# Adafruit_Airlift_Bitsy_Add-On.net
KiCad netlist of a schematic drawn in EAGLE
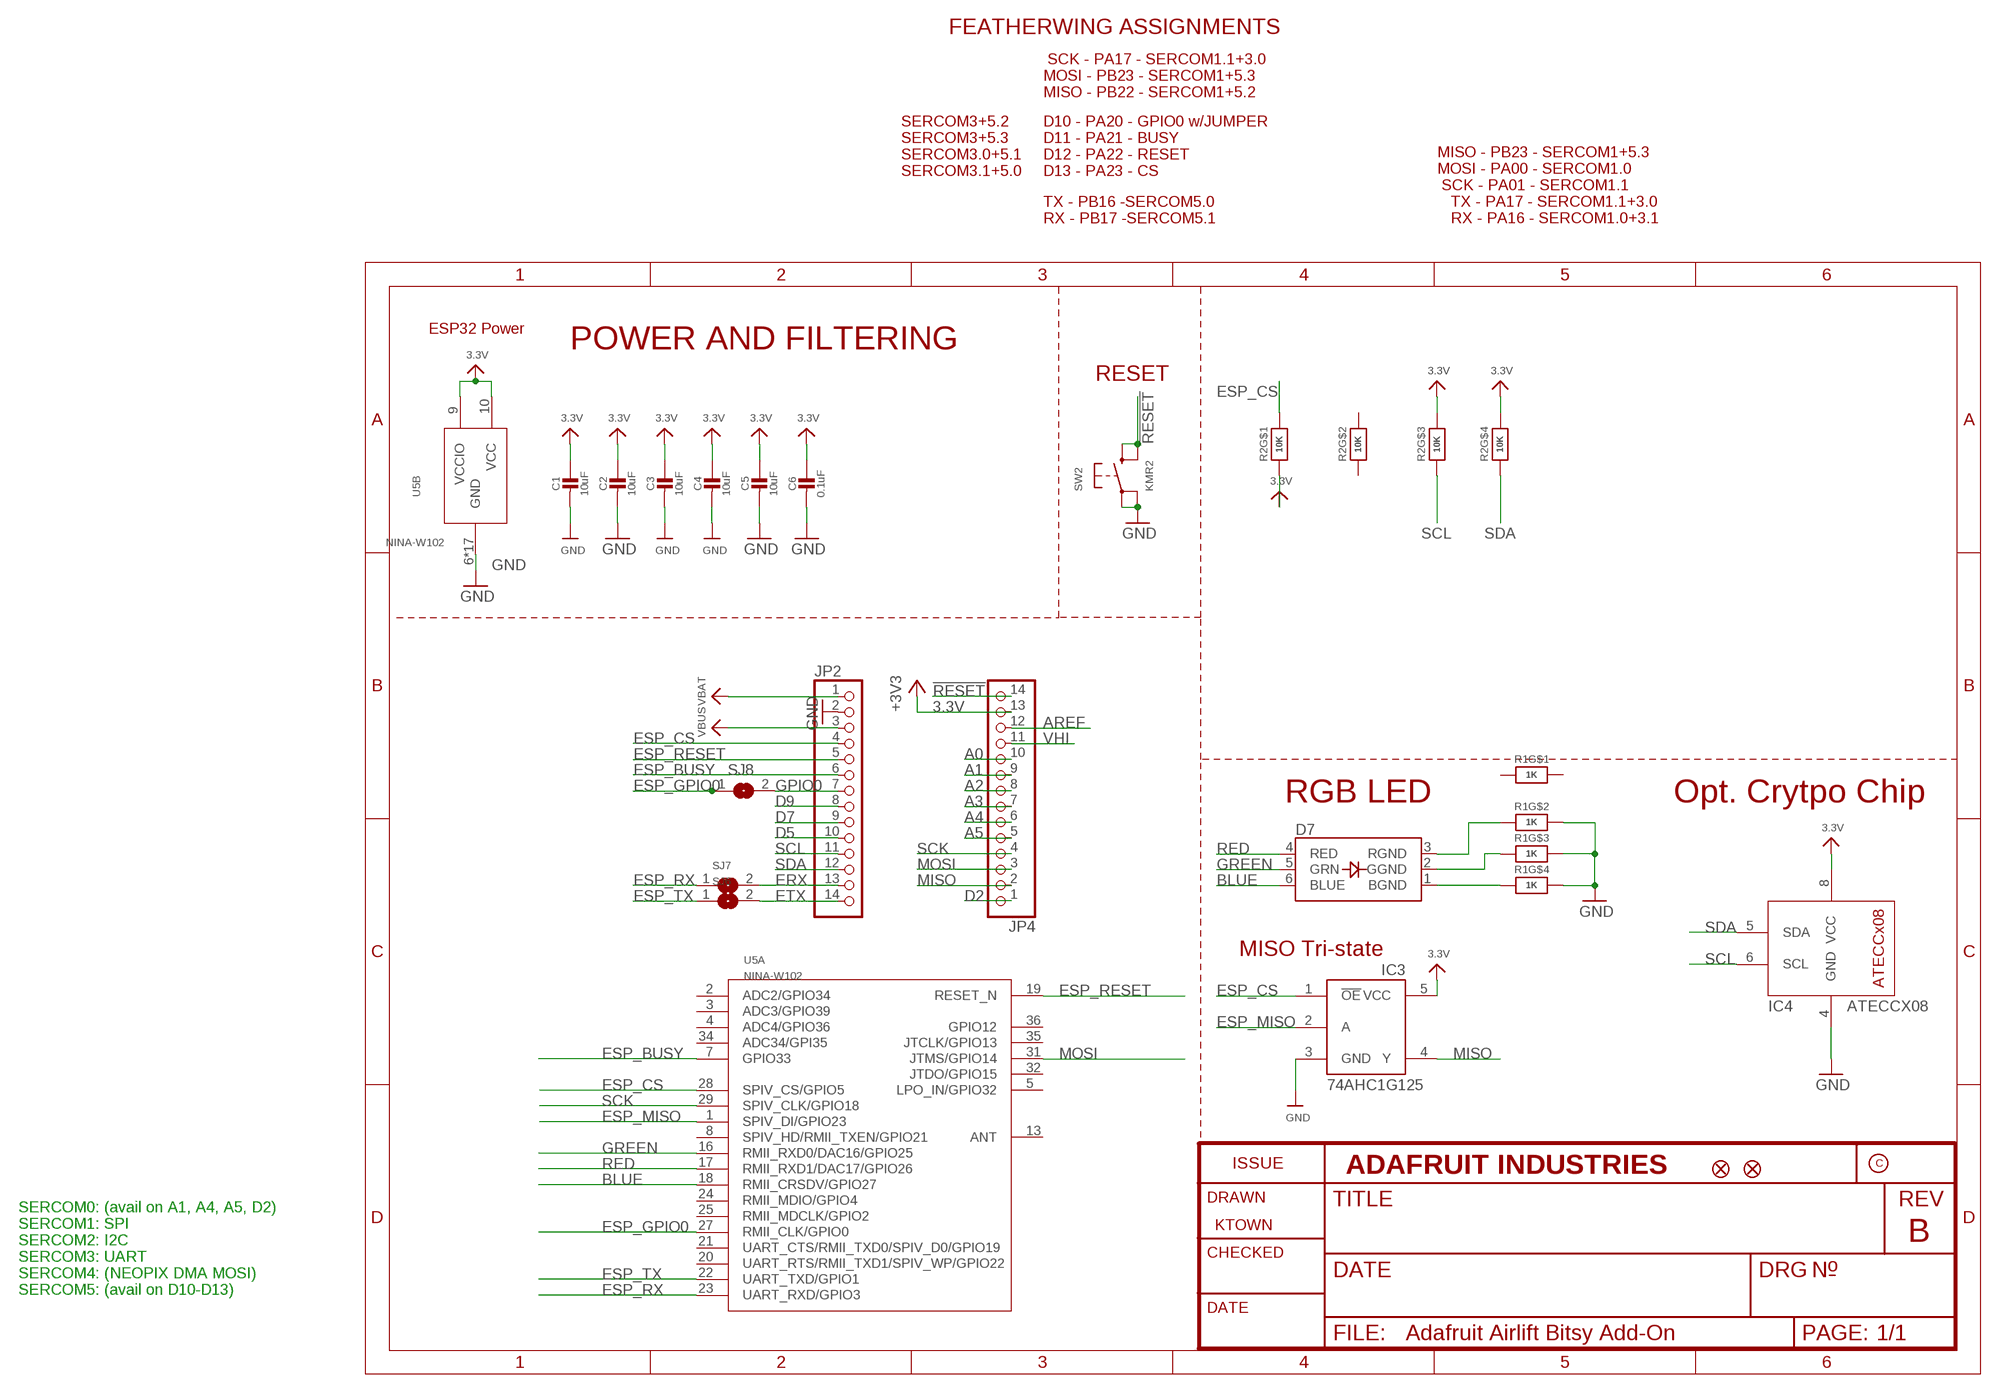
[diagram p0: schematic, sheet 1]

(export (version "E")
  (design (tool "Eeschema 10.0.6"))
  (components
    (comp (ref "C1")
      (value "10uF")
      (footprint "eagle-import:0805-NO")
      (libsource (lib "eagle-import") (part "CAP_CERAMIC0805-NOOUTLINE"))
    )
    (comp (ref "C2")
      (value "10uF")
      (footprint "eagle-import:0805-NO")
      (libsource (lib "eagle-import") (part "CAP_CERAMIC0805-NOOUTLINE"))
    )
    (comp (ref "C3")
      (value "10uF")
      (footprint "eagle-import:0805-NO")
      (libsource (lib "eagle-import") (part "CAP_CERAMIC0805-NOOUTLINE"))
    )
    (comp (ref "C4")
      (value "10uF")
      (footprint "eagle-import:0805-NO")
      (libsource (lib "eagle-import") (part "CAP_CERAMIC0805-NOOUTLINE"))
    )
    (comp (ref "C5")
      (value "10uF")
      (footprint "eagle-import:0805-NO")
      (libsource (lib "eagle-import") (part "CAP_CERAMIC0805-NOOUTLINE"))
    )
    (comp (ref "C6")
      (value "0.1uF")
      (footprint "eagle-import:0603-NO")
      (libsource (lib "eagle-import") (part "CAP_CERAMIC0603_NO"))
    )
    (comp (ref "D7")
      (value "LED_RGB_PLCC63535")
      (footprint "eagle-import:RGBLED_3535_PLCC6")
      (libsource (lib "eagle-import") (part "LED_RGB_PLCC63535"))
    )
    (comp (ref "IC3")
      (value "74AHC1G125")
      (footprint "eagle-import:SOT23-5L")
      (libsource (lib "eagle-import") (part "74AHC1G125"))
    )
    (comp (ref "IC4")
      (value "ATECCX08")
      (footprint "eagle-import:SOIC8_150MIL")
      (libsource (lib "eagle-import") (part "ATECCX08"))
    )
    (comp (ref "JP2")
      (value "HEADER-1X14")
      (footprint "eagle-import:1X14_ROUND70")
      (libsource (lib "eagle-import") (part "HEADER-1X14"))
    )
    (comp (ref "JP4")
      (value "HEADER-1X14")
      (footprint "eagle-import:1X14_ROUND70")
      (libsource (lib "eagle-import") (part "HEADER-1X14"))
    )
    (comp (ref "R1")
      (value "1K")
      (footprint "eagle-import:RESPACK_4X0603_NO")
      (libsource (lib "eagle-import") (part "RESISTOR_4PACK_NO"))
    )
    (comp (ref "R2")
      (value "10K")
      (footprint "eagle-import:RESPACK_4X0603_NO")
      (libsource (lib "eagle-import") (part "RESISTOR_4PACK_NO"))
    )
    (comp (ref "SJ6")
      (value "SOLDERJUMPER")
      (footprint "eagle-import:SOLDERJUMPER_ARROW_NOPASTE")
      (libsource (lib "eagle-import") (part "SOLDERJUMPER"))
    )
    (comp (ref "SJ7")
      (value "SOLDERJUMPER")
      (footprint "eagle-import:SOLDERJUMPER_ARROW_NOPASTE")
      (libsource (lib "eagle-import") (part "SOLDERJUMPER"))
    )
    (comp (ref "SJ8")
      (value "SOLDERJUMPER")
      (footprint "eagle-import:SOLDERJUMPER_ARROW_NOPASTE")
      (libsource (lib "eagle-import") (part "SOLDERJUMPER"))
    )
    (comp (ref "SW2")
      (value "KMR2")
      (footprint "eagle-import:BTN_KMR2_4.6X2.8")
      (libsource (lib "eagle-import") (part "SWITCH_TACT_SMT4.6X2.8"))
    )
    (comp (ref "U$34")
      (value "FIDUCIAL_1MM")
      (footprint "eagle-import:FIDUCIAL_1MM")
      (libsource (lib "eagle-import") (part "FIDUCIAL_1MM"))
    )
    (comp (ref "U$35")
      (value "FIDUCIAL_1MM")
      (footprint "eagle-import:FIDUCIAL_1MM")
      (libsource (lib "eagle-import") (part "FIDUCIAL_1MM"))
    )
    (comp (ref "U5")
      (value "NINA-W102")
      (footprint "eagle-import:ARDUINO-UCS&SOCS_NINA-W1X")
      (fields (field (name "MANUFACTURER") "Ublocks"))
      (libsource (lib "eagle-import") (part "NINA-W10XNINA-W10X-102"))
    )
  )
  (nets
    (net (code "1") (name "+3V3") (class "Default")
      (node (ref "C1") (pin "1") (pinfunction "1_1") (pintype "passive"))
      (node (ref "C2") (pin "1") (pinfunction "1_1") (pintype "passive"))
      (node (ref "C3") (pin "1") (pinfunction "1_1") (pintype "passive"))
      (node (ref "C4") (pin "1") (pinfunction "1_1") (pintype "passive"))
      (node (ref "C5") (pin "1") (pinfunction "1_1") (pintype "passive"))
      (node (ref "C6") (pin "1") (pinfunction "1_1") (pintype "passive"))
      (node (ref "IC3") (pin "5") (pinfunction "VCC_5") (pintype "power_in"))
      (node (ref "IC4") (pin "8") (pinfunction "VCC_8") (pintype "power_in"))
      (node (ref "JP4") (pin "13") (pinfunction "13_13") (pintype "passive"))
      (node (ref "R2") (pin "1") (pinfunction "1_1") (pintype "passive"))
      (node (ref "R2") (pin "5") (pinfunction "2_5") (pintype "passive"))
      (node (ref "R2") (pin "6") (pinfunction "2_6") (pintype "passive"))
      (node (ref "U5") (pin "10") (pinfunction "VCC_10") (pintype "bidirectional"))
      (node (ref "U5") (pin "9") (pinfunction "VCCIO_9") (pintype "bidirectional"))
    )
    (net (code "2") (name "/A0") (class "Default")
      (node (ref "JP4") (pin "10") (pinfunction "10_10") (pintype "passive"))
    )
    (net (code "3") (name "/A1") (class "Default")
      (node (ref "JP4") (pin "9") (pinfunction "9_9") (pintype "passive"))
    )
    (net (code "4") (name "/A2") (class "Default")
      (node (ref "JP4") (pin "8") (pinfunction "8_8") (pintype "passive"))
    )
    (net (code "5") (name "/A3") (class "Default")
      (node (ref "JP4") (pin "7") (pinfunction "7_7") (pintype "passive"))
    )
    (net (code "6") (name "/A4") (class "Default")
      (node (ref "JP4") (pin "6") (pinfunction "6_6") (pintype "passive"))
    )
    (net (code "7") (name "/A5") (class "Default")
      (node (ref "JP4") (pin "5") (pinfunction "5_5") (pintype "passive"))
    )
    (net (code "8") (name "/AREF") (class "Default")
      (node (ref "JP4") (pin "12") (pinfunction "12_12") (pintype "passive"))
    )
    (net (code "9") (name "/BLUE") (class "Default")
      (node (ref "D7") (pin "6") (pinfunction "BLUE_6") (pintype "bidirectional"))
      (node (ref "U5") (pin "18") (pinfunction "RMII_CRSDV/GPIO27_18") (pintype "bidirectional"))
    )
    (net (code "10") (name "/D2") (class "Default")
      (node (ref "JP4") (pin "1") (pinfunction "1_1") (pintype "passive"))
    )
    (net (code "11") (name "/D5") (class "Default")
      (node (ref "JP2") (pin "10") (pinfunction "10_10") (pintype "passive"))
    )
    (net (code "12") (name "/D7") (class "Default")
      (node (ref "JP2") (pin "9") (pinfunction "9_9") (pintype "passive"))
    )
    (net (code "13") (name "/D9") (class "Default")
      (node (ref "JP2") (pin "8") (pinfunction "8_8") (pintype "passive"))
    )
    (net (code "14") (name "/ERX") (class "Default")
      (node (ref "JP2") (pin "13") (pinfunction "13_13") (pintype "passive"))
      (node (ref "SJ7") (pin "2") (pinfunction "2_2") (pintype "passive"))
    )
    (net (code "15") (name "/ESP_BUSY") (class "Default")
      (node (ref "JP2") (pin "6") (pinfunction "6_6") (pintype "passive"))
      (node (ref "U5") (pin "7") (pinfunction "GPIO33_7") (pintype "bidirectional"))
    )
    (net (code "16") (name "/ESP_CS") (class "Default")
      (node (ref "IC3") (pin "1") (pinfunction "~{OE}_1") (pintype "input"))
      (node (ref "JP2") (pin "4") (pinfunction "4_4") (pintype "passive"))
      (node (ref "R2") (pin "8") (pinfunction "2_8") (pintype "passive"))
      (node (ref "U5") (pin "28") (pinfunction "SPIV_CS/GPIO5_28") (pintype "bidirectional"))
    )
    (net (code "17") (name "/ESP_GPIO0") (class "Default")
      (node (ref "SJ8") (pin "1") (pinfunction "1_1") (pintype "passive"))
      (node (ref "U5") (pin "27") (pinfunction "RMII_CLK/GPIO0_27") (pintype "bidirectional"))
    )
    (net (code "18") (name "/ESP_MISO") (class "Default")
      (node (ref "IC3") (pin "2") (pinfunction "A_2") (pintype "input"))
      (node (ref "U5") (pin "1") (pinfunction "SPIV_DI/GPIO23_1") (pintype "bidirectional"))
    )
    (net (code "19") (name "/ESP_RESET") (class "Default")
      (node (ref "JP2") (pin "5") (pinfunction "5_5") (pintype "passive"))
      (node (ref "U5") (pin "19") (pinfunction "RESET_N_19") (pintype "bidirectional"))
    )
    (net (code "20") (name "/ESP_RX") (class "Default")
      (node (ref "SJ7") (pin "1") (pinfunction "1_1") (pintype "passive"))
      (node (ref "U5") (pin "23") (pinfunction "UART_RXD/GPIO3_23") (pintype "bidirectional"))
    )
    (net (code "21") (name "/ESP_TX") (class "Default")
      (node (ref "SJ6") (pin "1") (pinfunction "1_1") (pintype "passive"))
      (node (ref "U5") (pin "22") (pinfunction "UART_TXD/GPIO1_22") (pintype "bidirectional"))
    )
    (net (code "22") (name "/ETX") (class "Default")
      (node (ref "JP2") (pin "14") (pinfunction "14_14") (pintype "passive"))
      (node (ref "SJ6") (pin "2") (pinfunction "2_2") (pintype "passive"))
    )
    (net (code "23") (name "/GPIO0") (class "Default")
      (node (ref "JP2") (pin "7") (pinfunction "7_7") (pintype "passive"))
      (node (ref "SJ8") (pin "2") (pinfunction "2_2") (pintype "passive"))
    )
    (net (code "24") (name "/GREEN") (class "Default")
      (node (ref "D7") (pin "5") (pinfunction "GRN_5") (pintype "bidirectional"))
      (node (ref "U5") (pin "16") (pinfunction "RMII_RXD0/DAC16/GPIO25_16") (pintype "bidirectional"))
    )
    (net (code "25") (name "/MISO") (class "Default")
      (node (ref "IC3") (pin "4") (pinfunction "Y_4") (pintype "output"))
      (node (ref "JP4") (pin "2") (pinfunction "2_2") (pintype "passive"))
    )
    (net (code "26") (name "/MOSI") (class "Default")
      (node (ref "JP4") (pin "3") (pinfunction "3_3") (pintype "passive"))
      (node (ref "U5") (pin "31") (pinfunction "JTMS/GPIO14_31") (pintype "bidirectional"))
    )
    (net (code "27") (name "/RED") (class "Default")
      (node (ref "D7") (pin "4") (pinfunction "RED_4") (pintype "bidirectional"))
      (node (ref "U5") (pin "17") (pinfunction "RMII_RXD1/DAC17/GPIO26_17") (pintype "bidirectional"))
    )
    (net (code "28") (name "/SCK") (class "Default")
      (node (ref "JP4") (pin "4") (pinfunction "4_4") (pintype "passive"))
      (node (ref "U5") (pin "29") (pinfunction "SPIV_CLK/GPIO18_29") (pintype "bidirectional"))
    )
    (net (code "29") (name "/SCL") (class "Default")
      (node (ref "IC4") (pin "6") (pinfunction "SCL_6") (pintype "bidirectional"))
      (node (ref "JP2") (pin "11") (pinfunction "11_11") (pintype "passive"))
      (node (ref "R2") (pin "3") (pinfunction "1_3") (pintype "passive"))
    )
    (net (code "30") (name "/SDA") (class "Default")
      (node (ref "IC4") (pin "5") (pinfunction "SDA_5") (pintype "bidirectional"))
      (node (ref "JP2") (pin "12") (pinfunction "12_12") (pintype "passive"))
      (node (ref "R2") (pin "4") (pinfunction "1_4") (pintype "passive"))
    )
    (net (code "31") (name "/VHI") (class "Default")
      (node (ref "JP4") (pin "11") (pinfunction "11_11") (pintype "passive"))
    )
    (net (code "32") (name "/~{RESET}") (class "Default")
      (node (ref "JP4") (pin "14") (pinfunction "14_14") (pintype "passive"))
      (node (ref "SW2") (pin "B") (pinfunction "S_B") (pintype "passive"))
      (node (ref "SW2") (pin "B'") (pinfunction "S1_B'") (pintype "passive"))
    )
    (net (code "33") (name "GND") (class "Default")
      (node (ref "C1") (pin "2") (pinfunction "2_2") (pintype "passive"))
      (node (ref "C2") (pin "2") (pinfunction "2_2") (pintype "passive"))
      (node (ref "C3") (pin "2") (pinfunction "2_2") (pintype "passive"))
      (node (ref "C4") (pin "2") (pinfunction "2_2") (pintype "passive"))
      (node (ref "C5") (pin "2") (pinfunction "2_2") (pintype "passive"))
      (node (ref "C6") (pin "2") (pinfunction "2_2") (pintype "passive"))
      (node (ref "IC3") (pin "3") (pinfunction "GND_3") (pintype "power_in"))
      (node (ref "IC4") (pin "4") (pinfunction "GND_4") (pintype "power_in"))
      (node (ref "JP2") (pin "2") (pinfunction "2_2") (pintype "passive"))
      (node (ref "R1") (pin "5") (pinfunction "2_5") (pintype "passive"))
      (node (ref "R1") (pin "6") (pinfunction "2_6") (pintype "passive"))
      (node (ref "R1") (pin "7") (pinfunction "2_7") (pintype "passive"))
      (node (ref "SW2") (pin "A") (pinfunction "P_A") (pintype "passive"))
      (node (ref "SW2") (pin "A'") (pinfunction "P1_A'") (pintype "passive"))
      (node (ref "U5") (pin "12") (pinfunction "GND_12") (pintype "bidirectional"))
      (node (ref "U5") (pin "14") (pinfunction "GND_14") (pintype "bidirectional"))
      (node (ref "U5") (pin "26") (pinfunction "GND_26") (pintype "bidirectional"))
      (node (ref "U5") (pin "30") (pinfunction "GND_30") (pintype "bidirectional"))
      (node (ref "U5") (pin "6") (pinfunction "GND_6") (pintype "bidirectional"))
      (node (ref "U5") (pin "GND@1") (pinfunction "GND_GND@1") (pintype "bidirectional"))
      (node (ref "U5") (pin "GND@10") (pinfunction "GND_GND@10") (pintype "bidirectional"))
      (node (ref "U5") (pin "GND@11") (pinfunction "GND_GND@11") (pintype "bidirectional"))
      (node (ref "U5") (pin "GND@12") (pinfunction "GND_GND@12") (pintype "bidirectional"))
      (node (ref "U5") (pin "GND@2") (pinfunction "GND_GND@2") (pintype "bidirectional"))
      (node (ref "U5") (pin "GND@3") (pinfunction "GND_GND@3") (pintype "bidirectional"))
      (node (ref "U5") (pin "GND@4") (pinfunction "GND_GND@4") (pintype "bidirectional"))
      (node (ref "U5") (pin "GND@5") (pinfunction "GND_GND@5") (pintype "bidirectional"))
      (node (ref "U5") (pin "GND@6") (pinfunction "GND_GND@6") (pintype "bidirectional"))
      (node (ref "U5") (pin "GND@7") (pinfunction "GND_GND@7") (pintype "bidirectional"))
      (node (ref "U5") (pin "GND@8") (pinfunction "GND_GND@8") (pintype "bidirectional"))
      (node (ref "U5") (pin "GND@9") (pinfunction "GND_GND@9") (pintype "bidirectional"))
    )
    (net (code "34") (name "Net-(D7-BGND)") (class "Default")
      (node (ref "D7") (pin "1") (pinfunction "BGND_1") (pintype "power_in"))
      (node (ref "R1") (pin "4") (pinfunction "1_4") (pintype "passive"))
    )
    (net (code "35") (name "Net-(D7-GGND)") (class "Default")
      (node (ref "D7") (pin "2") (pinfunction "GGND_2") (pintype "power_in"))
      (node (ref "R1") (pin "3") (pinfunction "1_3") (pintype "passive"))
    )
    (net (code "36") (name "Net-(D7-RGND)") (class "Default")
      (node (ref "D7") (pin "3") (pinfunction "RGND_3") (pintype "power_in"))
      (node (ref "R1") (pin "2") (pinfunction "1_2") (pintype "passive"))
    )
    (net (code "37") (name "VBAT") (class "Default")
      (node (ref "JP2") (pin "1") (pinfunction "1_1") (pintype "passive"))
    )
    (net (code "38") (name "VBUS") (class "Default")
      (node (ref "JP2") (pin "3") (pinfunction "3_3") (pintype "passive"))
    )
    (net (code "39") (name "unconnected-(R1-Pad1)") (class "Default")
      (node (ref "R1") (pin "1") (pinfunction "1_1") (pintype "passive"))
    )
    (net (code "40") (name "unconnected-(R1A-2-Pad8)") (class "Default")
      (node (ref "R1") (pin "8") (pinfunction "2_8") (pintype "passive"))
    )
    (net (code "41") (name "unconnected-(R2B-1-Pad2)") (class "Default")
      (node (ref "R2") (pin "2") (pinfunction "1_2") (pintype "passive"))
    )
    (net (code "42") (name "unconnected-(R2B-2-Pad7)") (class "Default")
      (node (ref "R2") (pin "7") (pinfunction "2_7") (pintype "passive"))
    )
    (net (code "43") (name "unconnected-(U5A-ADC2{slash}GPIO34-Pad2)") (class "Default")
      (node (ref "U5") (pin "2") (pinfunction "ADC2/GPIO34_2") (pintype "bidirectional"))
    )
    (net (code "44") (name "unconnected-(U5A-ADC3{slash}GPIO39-Pad3)") (class "Default")
      (node (ref "U5") (pin "3") (pinfunction "ADC3/GPIO39_3") (pintype "bidirectional"))
    )
    (net (code "45") (name "unconnected-(U5A-ADC4{slash}GPIO36-Pad4)") (class "Default")
      (node (ref "U5") (pin "4") (pinfunction "ADC4/GPIO36_4") (pintype "bidirectional"))
    )
    (net (code "46") (name "unconnected-(U5A-ADC34{slash}GPI35-Pad34)") (class "Default")
      (node (ref "U5") (pin "34") (pinfunction "ADC34/GPI35_34") (pintype "bidirectional"))
    )
    (net (code "47") (name "unconnected-(U5A-ANT-Pad13)") (class "Default")
      (node (ref "U5") (pin "13") (pinfunction "ANT_13") (pintype "bidirectional"))
    )
    (net (code "48") (name "unconnected-(U5A-GPIO12-Pad36)") (class "Default")
      (node (ref "U5") (pin "36") (pinfunction "GPIO12_36") (pintype "bidirectional"))
    )
    (net (code "49") (name "unconnected-(U5A-JTCLK{slash}GPIO13-Pad35)") (class "Default")
      (node (ref "U5") (pin "35") (pinfunction "JTCLK/GPIO13_35") (pintype "bidirectional"))
    )
    (net (code "50") (name "unconnected-(U5A-JTDO{slash}GPIO15-Pad32)") (class "Default")
      (node (ref "U5") (pin "32") (pinfunction "JTDO/GPIO15_32") (pintype "bidirectional"))
    )
    (net (code "51") (name "unconnected-(U5A-LPO_IN{slash}GPIO32-Pad5)") (class "Default")
      (node (ref "U5") (pin "5") (pinfunction "LPO_IN/GPIO32_5") (pintype "bidirectional"))
    )
    (net (code "52") (name "unconnected-(U5A-RMII_MDCLK{slash}GPIO2-Pad25)") (class "Default")
      (node (ref "U5") (pin "25") (pinfunction "RMII_MDCLK/GPIO2_25") (pintype "bidirectional"))
    )
    (net (code "53") (name "unconnected-(U5A-RMII_MDIO{slash}GPIO4-Pad24)") (class "Default")
      (node (ref "U5") (pin "24") (pinfunction "RMII_MDIO/GPIO4_24") (pintype "bidirectional"))
    )
    (net (code "54") (name "unconnected-(U5A-SPIV_HD{slash}RMII_TXEN{slash}GPIO21-Pad8)") (class "Default")
      (node (ref "U5") (pin "8") (pinfunction "SPIV_HD/RMII_TXEN/GPIO21_8") (pintype "bidirectional"))
    )
    (net (code "55") (name "unconnected-(U5A-UART_CTS{slash}RMII_TXD0{slash}SPIV_D0{slash}GPIO19-Pad21)") (class "Default")
      (node (ref "U5") (pin "21") (pinfunction "UART_CTS/RMII_TXD0/SPIV_D0/GPIO19_21") (pintype "bidirectional"))
    )
    (net (code "56") (name "unconnected-(U5A-UART_RTS{slash}RMII_TXD1{slash}SPIV_WP{slash}GPIO22-Pad20)") (class "Default")
      (node (ref "U5") (pin "20") (pinfunction "UART_RTS/RMII_TXD1/SPIV_WP/GPIO22_20") (pintype "bidirectional"))
    )
  )
)
